# DW1000Breakout.net
KiCad netlist of a schematic drawn in Altium Designer
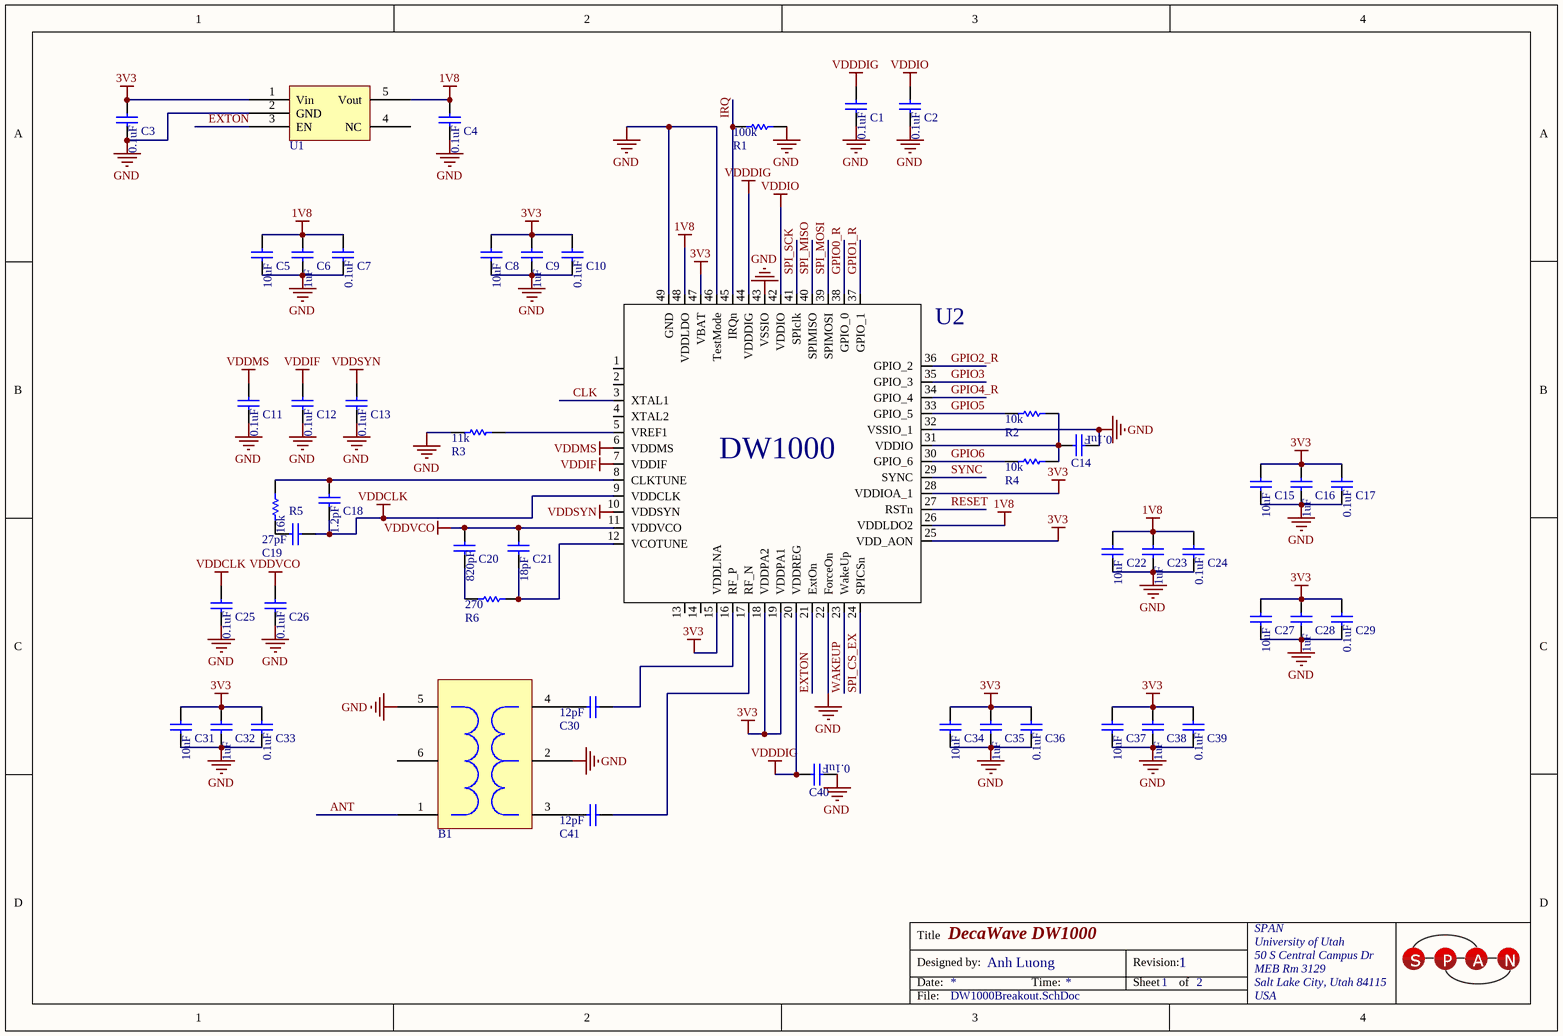
[diagram p0: DW1000Breakout.SchDoc]

(export (version "E")
  (design (tool "Eeschema 10.0.6"))
  (components
    (comp (ref "B1")
      (value "HHM1595A1")
      (footprint "BALUN")
      (description "XFMR BALUN RF 3.0-8.0GHZ UWB SMD")
      (fields (field (name "MANUFACTURER") "TDK Corporation"))
      (libsource (lib "DW1000Breakout") (part "HHM1595A1"))
    )
    (comp (ref "C1")
      (value "GRM188R71C104KA01D")
      (footprint "CAPC1608X08N (0603)")
      (description "CAP CER 0.1UF 16V 10% X7R 0603")
      (fields
        (field (name "MANUFACTURER") "Murata Electronics North America")
        (field (name "TOLERANCE") "±10%")
      )
      (libsource (lib "DW1000Breakout") (part "GRM188R71C104KA01D"))
    )
    (comp (ref "C2")
      (value "GRM188R71C104KA01D")
      (footprint "CAPC1608X08N (0603)")
      (description "CAP CER 0.1UF 16V 10% X7R 0603")
      (fields
        (field (name "MANUFACTURER") "Murata Electronics North America")
        (field (name "TOLERANCE") "±10%")
      )
      (libsource (lib "DW1000Breakout") (part "GRM188R71C104KA01D"))
    )
    (comp (ref "C3")
      (value "GRM188R71C104KA01D")
      (footprint "CAPC1608X08N (0603)")
      (description "CAP CER 0.1UF 16V 10% X7R 0603")
      (fields
        (field (name "MANUFACTURER") "Murata Electronics North America")
        (field (name "TOLERANCE") "±10%")
      )
      (libsource (lib "DW1000Breakout") (part "GRM188R71C104KA01D"))
    )
    (comp (ref "C4")
      (value "GRM188R71C104KA01D")
      (footprint "CAPC1608X08N (0603)")
      (description "CAP CER 0.1UF 16V 10% X7R 0603")
      (fields
        (field (name "MANUFACTURER") "Murata Electronics North America")
        (field (name "TOLERANCE") "±10%")
      )
      (libsource (lib "DW1000Breakout") (part "GRM188R71C104KA01D"))
    )
    (comp (ref "C5")
      (value "GRM188R60J106ME47D")
      (footprint "CAPC1608X08N (0603)")
      (description "CAP CER 10UF 6.3V 20% X5R 0603")
      (fields
        (field (name "MANUFACTURER") "Murata Electronics North America")
        (field (name "TOLERANCE") "±20%")
      )
      (libsource (lib "DWM1000Breakout") (part "GRM188R60J106ME47D"))
    )
    (comp (ref "C6")
      (value "GRM188R61A105KA61D")
      (footprint "CAPC1608X08N (0603)")
      (description "CAP CER 1UF 10V 10% X5R 0603")
      (fields
        (field (name "MANUFACTURER") "Murata Electronics North America")
        (field (name "TOLERANCE") "±10%")
      )
      (libsource (lib "DWM1000Breakout") (part "GRM188R61A105KA61D"))
    )
    (comp (ref "C7")
      (value "GRM188R71C104KA01D")
      (footprint "CAPC1608X08N (0603)")
      (description "CAP CER 0.1UF 16V 10% X7R 0603")
      (fields
        (field (name "MANUFACTURER") "Murata Electronics North America")
        (field (name "TOLERANCE") "±10%")
      )
      (libsource (lib "DWM1000Breakout") (part "GRM188R71C104KA01D"))
    )
    (comp (ref "C8")
      (value "GRM188R60J106ME47D")
      (footprint "CAPC1608X08N (0603)")
      (description "CAP CER 10UF 6.3V 20% X5R 0603")
      (fields
        (field (name "MANUFACTURER") "Murata Electronics North America")
        (field (name "TOLERANCE") "±20%")
      )
      (libsource (lib "DWM1000Breakout") (part "GRM188R60J106ME47D"))
    )
    (comp (ref "C9")
      (value "GRM188R61A105KA61D")
      (footprint "CAPC1608X08N (0603)")
      (description "CAP CER 1UF 10V 10% X5R 0603")
      (fields
        (field (name "MANUFACTURER") "Murata Electronics North America")
        (field (name "TOLERANCE") "±10%")
      )
      (libsource (lib "DWM1000Breakout") (part "GRM188R61A105KA61D"))
    )
    (comp (ref "C10")
      (value "GRM188R71C104KA01D")
      (footprint "CAPC1608X08N (0603)")
      (description "CAP CER 0.1UF 16V 10% X7R 0603")
      (fields
        (field (name "MANUFACTURER") "Murata Electronics North America")
        (field (name "TOLERANCE") "±10%")
      )
      (libsource (lib "DWM1000Breakout") (part "GRM188R71C104KA01D"))
    )
    (comp (ref "C11")
      (value "GRM188R71C104KA01D")
      (footprint "CAPC1608X08N (0603)")
      (description "CAP CER 0.1UF 16V 10% X7R 0603")
      (fields
        (field (name "MANUFACTURER") "Murata Electronics North America")
        (field (name "TOLERANCE") "±10%")
      )
      (libsource (lib "DW1000Breakout") (part "GRM188R71C104KA01D"))
    )
    (comp (ref "C12")
      (value "GRM188R71C104KA01D")
      (footprint "CAPC1608X08N (0603)")
      (description "CAP CER 0.1UF 16V 10% X7R 0603")
      (fields
        (field (name "MANUFACTURER") "Murata Electronics North America")
        (field (name "TOLERANCE") "±10%")
      )
      (libsource (lib "DW1000Breakout") (part "GRM188R71C104KA01D"))
    )
    (comp (ref "C13")
      (value "GRM188R71C104KA01D")
      (footprint "CAPC1608X08N (0603)")
      (description "CAP CER 0.1UF 16V 10% X7R 0603")
      (fields
        (field (name "MANUFACTURER") "Murata Electronics North America")
        (field (name "TOLERANCE") "±10%")
      )
      (libsource (lib "DW1000Breakout") (part "GRM188R71C104KA01D"))
    )
    (comp (ref "C14")
      (value "GRM188R71C104KA01D")
      (footprint "CAPC1608X08N (0603)")
      (description "CAP CER 0.1UF 16V 10% X7R 0603")
      (fields
        (field (name "MANUFACTURER") "Murata Electronics North America")
        (field (name "TOLERANCE") "±10%")
      )
      (libsource (lib "DW1000Breakout") (part "GRM188R71C104KA01D"))
    )
    (comp (ref "C15")
      (value "GRM188R60J106ME47D")
      (footprint "CAPC1608X08N (0603)")
      (description "CAP CER 10UF 6.3V 20% X5R 0603")
      (fields
        (field (name "MANUFACTURER") "Murata Electronics North America")
        (field (name "TOLERANCE") "±20%")
      )
      (libsource (lib "DWM1000Breakout") (part "GRM188R60J106ME47D"))
    )
    (comp (ref "C16")
      (value "GRM188R61A105KA61D")
      (footprint "CAPC1608X08N (0603)")
      (description "CAP CER 1UF 10V 10% X5R 0603")
      (fields
        (field (name "MANUFACTURER") "Murata Electronics North America")
        (field (name "TOLERANCE") "±10%")
      )
      (libsource (lib "DWM1000Breakout") (part "GRM188R61A105KA61D"))
    )
    (comp (ref "C17")
      (value "GRM188R71C104KA01D")
      (footprint "CAPC1608X08N (0603)")
      (description "CAP CER 0.1UF 16V 10% X7R 0603")
      (fields
        (field (name "MANUFACTURER") "Murata Electronics North America")
        (field (name "TOLERANCE") "±10%")
      )
      (libsource (lib "DWM1000Breakout") (part "GRM188R71C104KA01D"))
    )
    (comp (ref "C18")
      (value "GRM1885C1H1R2CA01D")
      (footprint "CAPC1608X08N (0603)")
      (description "CAP CER 1.2PF 50V NP0 0603")
      (fields
        (field (name "MANUFACTURER") "Murata Electronics North America")
        (field (name "TOLERANCE") "±0.25pF")
      )
      (libsource (lib "DW1000Breakout") (part "GRM1885C1H1R2CA01D"))
    )
    (comp (ref "C19")
      (value "GRM1885C1H270JA01D")
      (footprint "CAPC1608X08N (0603)")
      (description "CAP CER 27PF 50V NP0 0603")
      (fields
        (field (name "MANUFACTURER") "Murata Electronics North America")
        (field (name "TOLERANCE") "±5%")
      )
      (libsource (lib "DW1000Breakout") (part "GRM1885C1H270JA01D"))
    )
    (comp (ref "C20")
      (value "GRM188R71H821KA01D")
      (footprint "CAPC1608X08N (0603)")
      (description "CAP CER 820PF 50V X7R 0603")
      (fields
        (field (name "MANUFACTURER") "Murata Electronics North America")
        (field (name "TOLERANCE") "±10%")
      )
      (libsource (lib "DW1000Breakout") (part "GRM188R71H821KA01D"))
    )
    (comp (ref "C21")
      (value "GRM1885C1H180JA01D")
      (footprint "CAPC1608X08N (0603)")
      (description "CAP CER 18PF 50V NP0 0603")
      (fields
        (field (name "MANUFACTURER") "Murata Electronics North America")
        (field (name "TOLERANCE") "±5%")
      )
      (libsource (lib "DW1000Breakout") (part "GRM1885C1H180JA01D"))
    )
    (comp (ref "C22")
      (value "GRM188R60J106ME47D")
      (footprint "CAPC1608X08N (0603)")
      (description "CAP CER 10UF 6.3V 20% X5R 0603")
      (fields
        (field (name "MANUFACTURER") "Murata Electronics North America")
        (field (name "TOLERANCE") "±20%")
      )
      (libsource (lib "DWM1000Breakout") (part "GRM188R60J106ME47D"))
    )
    (comp (ref "C23")
      (value "GRM188R61A105KA61D")
      (footprint "CAPC1608X08N (0603)")
      (description "CAP CER 1UF 10V 10% X5R 0603")
      (fields
        (field (name "MANUFACTURER") "Murata Electronics North America")
        (field (name "TOLERANCE") "±10%")
      )
      (libsource (lib "DWM1000Breakout") (part "GRM188R61A105KA61D"))
    )
    (comp (ref "C24")
      (value "GRM188R71C104KA01D")
      (footprint "CAPC1608X08N (0603)")
      (description "CAP CER 0.1UF 16V 10% X7R 0603")
      (fields
        (field (name "MANUFACTURER") "Murata Electronics North America")
        (field (name "TOLERANCE") "±10%")
      )
      (libsource (lib "DWM1000Breakout") (part "GRM188R71C104KA01D"))
    )
    (comp (ref "C25")
      (value "GRM188R71C104KA01D")
      (footprint "CAPC1608X08N (0603)")
      (description "CAP CER 0.1UF 16V 10% X7R 0603")
      (fields
        (field (name "MANUFACTURER") "Murata Electronics North America")
        (field (name "TOLERANCE") "±10%")
      )
      (libsource (lib "DWM1000Breakout") (part "GRM188R71C104KA01D"))
    )
    (comp (ref "C26")
      (value "GRM188R71C104KA01D")
      (footprint "CAPC1608X08N (0603)")
      (description "CAP CER 0.1UF 16V 10% X7R 0603")
      (fields
        (field (name "MANUFACTURER") "Murata Electronics North America")
        (field (name "TOLERANCE") "±10%")
      )
      (libsource (lib "DWM1000Breakout") (part "GRM188R71C104KA01D"))
    )
    (comp (ref "C27")
      (value "GRM188R60J106ME47D")
      (footprint "CAPC1608X08N (0603)")
      (description "CAP CER 10UF 6.3V 20% X5R 0603")
      (fields
        (field (name "MANUFACTURER") "Murata Electronics North America")
        (field (name "TOLERANCE") "±20%")
      )
      (libsource (lib "DWM1000Breakout") (part "GRM188R60J106ME47D"))
    )
    (comp (ref "C28")
      (value "GRM188R61A105KA61D")
      (footprint "CAPC1608X08N (0603)")
      (description "CAP CER 1UF 10V 10% X5R 0603")
      (fields
        (field (name "MANUFACTURER") "Murata Electronics North America")
        (field (name "TOLERANCE") "±10%")
      )
      (libsource (lib "DWM1000Breakout") (part "GRM188R61A105KA61D"))
    )
    (comp (ref "C29")
      (value "GRM188R71C104KA01D")
      (footprint "CAPC1608X08N (0603)")
      (description "CAP CER 0.1UF 16V 10% X7R 0603")
      (fields
        (field (name "MANUFACTURER") "Murata Electronics North America")
        (field (name "TOLERANCE") "±10%")
      )
      (libsource (lib "DWM1000Breakout") (part "GRM188R71C104KA01D"))
    )
    (comp (ref "C30")
      (value "GRM1885C1H120JA01D")
      (footprint "CAPC1608X08N (0603)")
      (description "CAP CER 12PF 50V NP0 0603")
      (fields
        (field (name "MANUFACTURER") "Murata Electronics North America")
        (field (name "TOLERANCE") "±5%")
      )
      (libsource (lib "DW1000Breakout") (part "GRM1885C1H120JA01D"))
    )
    (comp (ref "C31")
      (value "GRM188R60J106ME47D")
      (footprint "CAPC1608X08N (0603)")
      (description "CAP CER 10UF 6.3V 20% X5R 0603")
      (fields
        (field (name "MANUFACTURER") "Murata Electronics North America")
        (field (name "TOLERANCE") "±20%")
      )
      (libsource (lib "DWM1000Breakout") (part "GRM188R60J106ME47D"))
    )
    (comp (ref "C32")
      (value "GRM188R61A105KA61D")
      (footprint "CAPC1608X08N (0603)")
      (description "CAP CER 1UF 10V 10% X5R 0603")
      (fields
        (field (name "MANUFACTURER") "Murata Electronics North America")
        (field (name "TOLERANCE") "±10%")
      )
      (libsource (lib "DWM1000Breakout") (part "GRM188R61A105KA61D"))
    )
    (comp (ref "C33")
      (value "GRM188R71C104KA01D")
      (footprint "CAPC1608X08N (0603)")
      (description "CAP CER 0.1UF 16V 10% X7R 0603")
      (fields
        (field (name "MANUFACTURER") "Murata Electronics North America")
        (field (name "TOLERANCE") "±10%")
      )
      (libsource (lib "DWM1000Breakout") (part "GRM188R71C104KA01D"))
    )
    (comp (ref "C34")
      (value "GRM188R60J106ME47D")
      (footprint "CAPC1608X08N (0603)")
      (description "CAP CER 10UF 6.3V 20% X5R 0603")
      (fields
        (field (name "MANUFACTURER") "Murata Electronics North America")
        (field (name "TOLERANCE") "±20%")
      )
      (libsource (lib "DWM1000Breakout") (part "GRM188R60J106ME47D"))
    )
    (comp (ref "C35")
      (value "GRM188R61A105KA61D")
      (footprint "CAPC1608X08N (0603)")
      (description "CAP CER 1UF 10V 10% X5R 0603")
      (fields
        (field (name "MANUFACTURER") "Murata Electronics North America")
        (field (name "TOLERANCE") "±10%")
      )
      (libsource (lib "DWM1000Breakout") (part "GRM188R61A105KA61D"))
    )
    (comp (ref "C36")
      (value "GRM188R71C104KA01D")
      (footprint "CAPC1608X08N (0603)")
      (description "CAP CER 0.1UF 16V 10% X7R 0603")
      (fields
        (field (name "MANUFACTURER") "Murata Electronics North America")
        (field (name "TOLERANCE") "±10%")
      )
      (libsource (lib "DWM1000Breakout") (part "GRM188R71C104KA01D"))
    )
    (comp (ref "C37")
      (value "GRM188R60J106ME47D")
      (footprint "CAPC1608X08N (0603)")
      (description "CAP CER 10UF 6.3V 20% X5R 0603")
      (fields
        (field (name "MANUFACTURER") "Murata Electronics North America")
        (field (name "TOLERANCE") "±20%")
      )
      (libsource (lib "DWM1000Breakout") (part "GRM188R60J106ME47D"))
    )
    (comp (ref "C38")
      (value "GRM188R61A105KA61D")
      (footprint "CAPC1608X08N (0603)")
      (description "CAP CER 1UF 10V 10% X5R 0603")
      (fields
        (field (name "MANUFACTURER") "Murata Electronics North America")
        (field (name "TOLERANCE") "±10%")
      )
      (libsource (lib "DWM1000Breakout") (part "GRM188R61A105KA61D"))
    )
    (comp (ref "C39")
      (value "GRM188R71C104KA01D")
      (footprint "CAPC1608X08N (0603)")
      (description "CAP CER 0.1UF 16V 10% X7R 0603")
      (fields
        (field (name "MANUFACTURER") "Murata Electronics North America")
        (field (name "TOLERANCE") "±10%")
      )
      (libsource (lib "DWM1000Breakout") (part "GRM188R71C104KA01D"))
    )
    (comp (ref "C40")
      (value "GRM188R71C104KA01D")
      (footprint "CAPC1608X08N (0603)")
      (description "CAP CER 0.1UF 16V 10% X7R 0603")
      (fields
        (field (name "MANUFACTURER") "Murata Electronics North America")
        (field (name "TOLERANCE") "±10%")
      )
      (libsource (lib "DW1000Breakout") (part "GRM188R71C104KA01D"))
    )
    (comp (ref "C41")
      (value "GRM1885C1H120JA01D")
      (footprint "CAPC1608X08N (0603)")
      (description "CAP CER 12PF 50V NP0 0603")
      (fields
        (field (name "MANUFACTURER") "Murata Electronics North America")
        (field (name "TOLERANCE") "±5%")
      )
      (libsource (lib "DW1000Breakout") (part "GRM1885C1H120JA01D"))
    )
    (comp (ref "R1")
      (value "MCR03ERTJ104")
      (footprint "RESC1608X06N (0603)")
      (description "RES SMD 100K OHM 5% 1/10W 0603")
      (fields (field (name "MANUFACTURER") "Rohm Semiconductor") (field (name "TOLERANCE") "±5%"))
      (libsource (lib "DW1000Breakout") (part "MCR03ERTJ104"))
    )
    (comp (ref "R2")
      (value "MCR03ERTJ103")
      (footprint "RESC1608X06N (0603)")
      (description "RES 10K OHM 1/10W 5% 0603 SMD")
      (fields (field (name "MANUFACTURER") "Rohm Semiconductor") (field (name "TOLERANCE") "±5%"))
      (libsource (lib "DW1000Breakout") (part "MCR03ERTJ103"))
    )
    (comp (ref "R3")
      (value "MCR03ERTJ113")
      (footprint "RESC1608X06N (0603)")
      (description "RES SMD 11K OHM 5% 1/10W 0603")
      (fields (field (name "MANUFACTURER") "Rohm Semiconductor") (field (name "TOLERANCE") "±5%"))
      (libsource (lib "DW1000Breakout") (part "MCR03ERTJ113"))
    )
    (comp (ref "R4")
      (value "MCR03ERTJ103")
      (footprint "RESC1608X06N (0603)")
      (description "RES 10K OHM 1/10W 5% 0603 SMD")
      (fields (field (name "MANUFACTURER") "Rohm Semiconductor") (field (name "TOLERANCE") "±5%"))
      (libsource (lib "DW1000Breakout") (part "MCR03ERTJ103"))
    )
    (comp (ref "R5")
      (value "MCR03ERTJ163")
      (footprint "RESC1608X06N (0603)")
      (description "RES SMD 16K OHM 5% 1/10W 0603")
      (fields (field (name "MANUFACTURER") "Rohm Semiconductor") (field (name "TOLERANCE") "±5%"))
      (libsource (lib "DW1000Breakout") (part "MCR03ERTJ163"))
    )
    (comp (ref "R6")
      (value "MCR03ERTJ271")
      (footprint "RESC1608X06N (0603)")
      (description "RES SMD 270 OHM 5% 1/10W 0603")
      (fields (field (name "MANUFACTURER") "Rohm Semiconductor") (field (name "TOLERANCE") "±5%"))
      (libsource (lib "DW1000Breakout") (part "MCR03ERTJ271"))
    )
    (comp (ref "U1")
      (value "LP5907MFX-1.8/NOPB")
      (footprint "SOT95P280X145-5N")
      (description "IC REG LDO 1.8V 0.25A SOT23-5")
      (fields (field (name "MANUFACTURER") "Texas Instruments"))
      (libsource (lib "DW1000Breakout") (part "LP5907MFX-1.8/NOPB"))
    )
    (comp (ref "U2")
      (value "DW1000 IC")
      (footprint "QFN-48")
      (description "UWB DW1000")
      (fields (field (name "PART NUMBER") "DW1000_QFN") (field (name "MANUFACTURER") "Decawave Ltd."))
      (libsource (lib "DW1000") (part "DW1000_QFN_48"))
    )
  )
  (nets
    (net (code "1") (name "/ANT") (class "Default")
      (node (ref "B1") (pin "1") (pinfunction "1_1") (pintype "passive"))
    )
    (net (code "2") (name "/CLK") (class "Default")
      (node (ref "U2") (pin "3") (pinfunction "XTAL1_3") (pintype "passive"))
    )
    (net (code "3") (name "/EXTON") (class "Default")
      (node (ref "U1") (pin "3") (pinfunction "EN_3") (pintype "passive"))
      (node (ref "U2") (pin "21") (pinfunction "ExtOn_21") (pintype "passive"))
    )
    (net (code "4") (name "/GPIO0_R") (class "Default")
      (node (ref "U2") (pin "38") (pinfunction "GPIO_0_38") (pintype "passive"))
    )
    (net (code "5") (name "/GPIO1_R") (class "Default")
      (node (ref "U2") (pin "37") (pinfunction "GPIO_1_37") (pintype "passive"))
    )
    (net (code "6") (name "/GPIO2_R") (class "Default")
      (node (ref "U2") (pin "36") (pinfunction "GPIO_2_36") (pintype "passive"))
    )
    (net (code "7") (name "/GPIO3") (class "Default")
      (node (ref "U2") (pin "35") (pinfunction "GPIO_3_35") (pintype "passive"))
    )
    (net (code "8") (name "/GPIO4_R") (class "Default")
      (node (ref "U2") (pin "34") (pinfunction "GPIO_4_34") (pintype "passive"))
    )
    (net (code "9") (name "/GPIO5") (class "Default")
      (node (ref "R2") (pin "1") (pinfunction "1_1") (pintype "passive"))
      (node (ref "U2") (pin "33") (pinfunction "GPIO_5_33") (pintype "passive"))
    )
    (net (code "10") (name "/GPIO6") (class "Default")
      (node (ref "R4") (pin "1") (pinfunction "1_1") (pintype "passive"))
      (node (ref "U2") (pin "30") (pinfunction "GPIO_6_30") (pintype "passive"))
    )
    (net (code "11") (name "/IRQ") (class "Default")
      (node (ref "R1") (pin "1") (pinfunction "1_1") (pintype "passive"))
      (node (ref "U2") (pin "45") (pinfunction "IRQn_45") (pintype "passive"))
    )
    (net (code "12") (name "/RESET") (class "Default")
      (node (ref "U2") (pin "27") (pinfunction "RSTn_27") (pintype "passive"))
    )
    (net (code "13") (name "/SPI_CS_EX") (class "Default")
      (node (ref "U2") (pin "24") (pinfunction "SPICSn_24") (pintype "passive"))
    )
    (net (code "14") (name "/SPI_MISO") (class "Default")
      (node (ref "U2") (pin "40") (pinfunction "SPIMISO_40") (pintype "passive"))
    )
    (net (code "15") (name "/SPI_MOSI") (class "Default")
      (node (ref "U2") (pin "39") (pinfunction "SPIMOSI_39") (pintype "passive"))
    )
    (net (code "16") (name "/SPI_SCK") (class "Default")
      (node (ref "U2") (pin "41") (pinfunction "SPIclk_41") (pintype "passive"))
    )
    (net (code "17") (name "/SYNC") (class "Default")
      (node (ref "U2") (pin "29") (pinfunction "SYNC_29") (pintype "passive"))
    )
    (net (code "18") (name "/WAKEUP") (class "Default")
      (node (ref "U2") (pin "23") (pinfunction "WakeUp_23") (pintype "passive"))
    )
    (net (code "19") (name "1V8") (class "Default")
      (node (ref "C22") (pin "2") (pinfunction "2_2") (pintype "passive"))
      (node (ref "C23") (pin "2") (pinfunction "2_2") (pintype "passive"))
      (node (ref "C24") (pin "2") (pinfunction "2_2") (pintype "passive"))
      (node (ref "C4") (pin "2") (pinfunction "2_2") (pintype "passive"))
      (node (ref "C5") (pin "2") (pinfunction "2_2") (pintype "passive"))
      (node (ref "C6") (pin "2") (pinfunction "2_2") (pintype "passive"))
      (node (ref "C7") (pin "2") (pinfunction "2_2") (pintype "passive"))
      (node (ref "U1") (pin "5") (pinfunction "Vout_5") (pintype "passive"))
      (node (ref "U2") (pin "26") (pinfunction "VDDLDO2_26") (pintype "passive"))
      (node (ref "U2") (pin "48") (pinfunction "VDDLDO_48") (pintype "passive"))
    )
    (net (code "20") (name "3V3") (class "Default")
      (node (ref "C10") (pin "2") (pinfunction "2_2") (pintype "passive"))
      (node (ref "C15") (pin "2") (pinfunction "2_2") (pintype "passive"))
      (node (ref "C16") (pin "2") (pinfunction "2_2") (pintype "passive"))
      (node (ref "C17") (pin "2") (pinfunction "2_2") (pintype "passive"))
      (node (ref "C27") (pin "2") (pinfunction "2_2") (pintype "passive"))
      (node (ref "C28") (pin "2") (pinfunction "2_2") (pintype "passive"))
      (node (ref "C29") (pin "2") (pinfunction "2_2") (pintype "passive"))
      (node (ref "C3") (pin "2") (pinfunction "2_2") (pintype "passive"))
      (node (ref "C31") (pin "2") (pinfunction "2_2") (pintype "passive"))
      (node (ref "C32") (pin "2") (pinfunction "2_2") (pintype "passive"))
      (node (ref "C33") (pin "2") (pinfunction "2_2") (pintype "passive"))
      (node (ref "C34") (pin "2") (pinfunction "2_2") (pintype "passive"))
      (node (ref "C35") (pin "2") (pinfunction "2_2") (pintype "passive"))
      (node (ref "C36") (pin "2") (pinfunction "2_2") (pintype "passive"))
      (node (ref "C37") (pin "2") (pinfunction "2_2") (pintype "passive"))
      (node (ref "C38") (pin "2") (pinfunction "2_2") (pintype "passive"))
      (node (ref "C39") (pin "2") (pinfunction "2_2") (pintype "passive"))
      (node (ref "C8") (pin "2") (pinfunction "2_2") (pintype "passive"))
      (node (ref "C9") (pin "2") (pinfunction "2_2") (pintype "passive"))
      (node (ref "U1") (pin "1") (pinfunction "Vin_1") (pintype "passive"))
      (node (ref "U2") (pin "15") (pinfunction "VDDLNA_15") (pintype "passive"))
      (node (ref "U2") (pin "18") (pinfunction "VDDPA2_18") (pintype "passive"))
      (node (ref "U2") (pin "19") (pinfunction "VDDPA1_19") (pintype "passive"))
      (node (ref "U2") (pin "25") (pinfunction "VDD_AON_25") (pintype "passive"))
      (node (ref "U2") (pin "28") (pinfunction "VDDIOA_1_28") (pintype "passive"))
      (node (ref "U2") (pin "47") (pinfunction "VBAT_47") (pintype "passive"))
    )
    (net (code "21") (name "GND") (class "Default")
      (node (ref "B1") (pin "2") (pinfunction "2_2") (pintype "passive"))
      (node (ref "B1") (pin "5") (pinfunction "5_5") (pintype "passive"))
      (node (ref "C1") (pin "1") (pinfunction "1_1") (pintype "passive"))
      (node (ref "C10") (pin "1") (pinfunction "1_1") (pintype "passive"))
      (node (ref "C11") (pin "1") (pinfunction "1_1") (pintype "passive"))
      (node (ref "C12") (pin "1") (pinfunction "1_1") (pintype "passive"))
      (node (ref "C13") (pin "1") (pinfunction "1_1") (pintype "passive"))
      (node (ref "C14") (pin "1") (pinfunction "1_1") (pintype "passive"))
      (node (ref "C15") (pin "1") (pinfunction "1_1") (pintype "passive"))
      (node (ref "C16") (pin "1") (pinfunction "1_1") (pintype "passive"))
      (node (ref "C17") (pin "1") (pinfunction "1_1") (pintype "passive"))
      (node (ref "C2") (pin "1") (pinfunction "1_1") (pintype "passive"))
      (node (ref "C22") (pin "1") (pinfunction "1_1") (pintype "passive"))
      (node (ref "C23") (pin "1") (pinfunction "1_1") (pintype "passive"))
      (node (ref "C24") (pin "1") (pinfunction "1_1") (pintype "passive"))
      (node (ref "C25") (pin "1") (pinfunction "1_1") (pintype "passive"))
      (node (ref "C26") (pin "1") (pinfunction "1_1") (pintype "passive"))
      (node (ref "C27") (pin "1") (pinfunction "1_1") (pintype "passive"))
      (node (ref "C28") (pin "1") (pinfunction "1_1") (pintype "passive"))
      (node (ref "C29") (pin "1") (pinfunction "1_1") (pintype "passive"))
      (node (ref "C3") (pin "1") (pinfunction "1_1") (pintype "passive"))
      (node (ref "C31") (pin "1") (pinfunction "1_1") (pintype "passive"))
      (node (ref "C32") (pin "1") (pinfunction "1_1") (pintype "passive"))
      (node (ref "C33") (pin "1") (pinfunction "1_1") (pintype "passive"))
      (node (ref "C34") (pin "1") (pinfunction "1_1") (pintype "passive"))
      (node (ref "C35") (pin "1") (pinfunction "1_1") (pintype "passive"))
      (node (ref "C36") (pin "1") (pinfunction "1_1") (pintype "passive"))
      (node (ref "C37") (pin "1") (pinfunction "1_1") (pintype "passive"))
      (node (ref "C38") (pin "1") (pinfunction "1_1") (pintype "passive"))
      (node (ref "C39") (pin "1") (pinfunction "1_1") (pintype "passive"))
      (node (ref "C4") (pin "1") (pinfunction "1_1") (pintype "passive"))
      (node (ref "C40") (pin "1") (pinfunction "1_1") (pintype "passive"))
      (node (ref "C5") (pin "1") (pinfunction "1_1") (pintype "passive"))
      (node (ref "C6") (pin "1") (pinfunction "1_1") (pintype "passive"))
      (node (ref "C7") (pin "1") (pinfunction "1_1") (pintype "passive"))
      (node (ref "C8") (pin "1") (pinfunction "1_1") (pintype "passive"))
      (node (ref "C9") (pin "1") (pinfunction "1_1") (pintype "passive"))
      (node (ref "R1") (pin "2") (pinfunction "2_2") (pintype "passive"))
      (node (ref "R3") (pin "1") (pinfunction "1_1") (pintype "passive"))
      (node (ref "U1") (pin "2") (pinfunction "GND_2") (pintype "passive"))
      (node (ref "U2") (pin "22") (pinfunction "ForceOn_22") (pintype "passive"))
      (node (ref "U2") (pin "32") (pinfunction "VSSIO_1_32") (pintype "passive"))
      (node (ref "U2") (pin "43") (pinfunction "VSSIO_43") (pintype "passive"))
      (node (ref "U2") (pin "46") (pinfunction "TestMode_46") (pintype "passive"))
      (node (ref "U2") (pin "49") (pinfunction "GND_49") (pintype "passive"))
    )
    (net (code "22") (name "Net-(B1-Pad3)") (class "Default")
      (node (ref "B1") (pin "3") (pinfunction "3_3") (pintype "passive"))
      (node (ref "C41") (pin "1") (pinfunction "1_1") (pintype "passive"))
    )
    (net (code "23") (name "Net-(B1-Pad4)") (class "Default")
      (node (ref "B1") (pin "4") (pinfunction "4_4") (pintype "passive"))
      (node (ref "C30") (pin "1") (pinfunction "1_1") (pintype "passive"))
    )
    (net (code "24") (name "Net-(C14-Pad2)") (class "Default")
      (node (ref "C14") (pin "2") (pinfunction "2_2") (pintype "passive"))
      (node (ref "R2") (pin "2") (pinfunction "2_2") (pintype "passive"))
      (node (ref "R4") (pin "2") (pinfunction "2_2") (pintype "passive"))
      (node (ref "U2") (pin "31") (pinfunction "VDDIO_31") (pintype "passive"))
    )
    (net (code "25") (name "Net-(C19-Pad1)") (class "Default")
      (node (ref "C19") (pin "1") (pinfunction "1_1") (pintype "passive"))
      (node (ref "R5") (pin "1") (pinfunction "1_1") (pintype "passive"))
    )
    (net (code "26") (name "Net-(C20-Pad1)") (class "Default")
      (node (ref "C20") (pin "1") (pinfunction "1_1") (pintype "passive"))
      (node (ref "R6") (pin "1") (pinfunction "1_1") (pintype "passive"))
    )
    (net (code "27") (name "Net-(U2-CLKTUNE)") (class "Default")
      (node (ref "C18") (pin "2") (pinfunction "2_2") (pintype "passive"))
      (node (ref "R5") (pin "2") (pinfunction "2_2") (pintype "passive"))
      (node (ref "U2") (pin "8") (pinfunction "CLKTUNE_8") (pintype "passive"))
    )
    (net (code "28") (name "Net-(U2-RF_N)") (class "Default")
      (node (ref "C41") (pin "2") (pinfunction "2_2") (pintype "passive"))
      (node (ref "U2") (pin "17") (pinfunction "RF_N_17") (pintype "passive"))
    )
    (net (code "29") (name "Net-(U2-RF_P)") (class "Default")
      (node (ref "C30") (pin "2") (pinfunction "2_2") (pintype "passive"))
      (node (ref "U2") (pin "16") (pinfunction "RF_P_16") (pintype "passive"))
    )
    (net (code "30") (name "Net-(U2-VCOTUNE)") (class "Default")
      (node (ref "C21") (pin "1") (pinfunction "1_1") (pintype "passive"))
      (node (ref "R6") (pin "2") (pinfunction "2_2") (pintype "passive"))
      (node (ref "U2") (pin "12") (pinfunction "VCOTUNE_12") (pintype "passive"))
    )
    (net (code "31") (name "Net-(U2-VREF1)") (class "Default")
      (node (ref "R3") (pin "2") (pinfunction "2_2") (pintype "passive"))
      (node (ref "U2") (pin "5") (pinfunction "VREF1_5") (pintype "passive"))
    )
    (net (code "32") (name "VDDCLK") (class "Default")
      (node (ref "C18") (pin "1") (pinfunction "1_1") (pintype "passive"))
      (node (ref "C19") (pin "2") (pinfunction "2_2") (pintype "passive"))
      (node (ref "C25") (pin "2") (pinfunction "2_2") (pintype "passive"))
      (node (ref "U2") (pin "9") (pinfunction "VDDCLK_9") (pintype "passive"))
    )
    (net (code "33") (name "VDDDIG") (class "Default")
      (node (ref "C1") (pin "2") (pinfunction "2_2") (pintype "passive"))
      (node (ref "C40") (pin "2") (pinfunction "2_2") (pintype "passive"))
      (node (ref "U2") (pin "20") (pinfunction "VDDREG_20") (pintype "passive"))
      (node (ref "U2") (pin "44") (pinfunction "VDDDIG_44") (pintype "passive"))
    )
    (net (code "34") (name "VDDIF") (class "Default")
      (node (ref "C12") (pin "2") (pinfunction "2_2") (pintype "passive"))
      (node (ref "U2") (pin "7") (pinfunction "VDDIF_7") (pintype "passive"))
    )
    (net (code "35") (name "VDDIO") (class "Default")
      (node (ref "C2") (pin "2") (pinfunction "2_2") (pintype "passive"))
      (node (ref "U2") (pin "42") (pinfunction "VDDIO_42") (pintype "passive"))
    )
    (net (code "36") (name "VDDMS") (class "Default")
      (node (ref "C11") (pin "2") (pinfunction "2_2") (pintype "passive"))
      (node (ref "U2") (pin "6") (pinfunction "VDDMS_6") (pintype "passive"))
    )
    (net (code "37") (name "VDDSYN") (class "Default")
      (node (ref "C13") (pin "2") (pinfunction "2_2") (pintype "passive"))
      (node (ref "U2") (pin "10") (pinfunction "VDDSYN_10") (pintype "passive"))
    )
    (net (code "38") (name "VDDVCO") (class "Default")
      (node (ref "C20") (pin "2") (pinfunction "2_2") (pintype "passive"))
      (node (ref "C21") (pin "2") (pinfunction "2_2") (pintype "passive"))
      (node (ref "C26") (pin "2") (pinfunction "2_2") (pintype "passive"))
      (node (ref "U2") (pin "11") (pinfunction "VDDVCO_11") (pintype "passive"))
    )
    (net (code "39") (name "unconnected-(B1-Pad6)") (class "Default")
      (node (ref "B1") (pin "6") (pinfunction "6_6") (pintype "passive"))
    )
    (net (code "40") (name "unconnected-(U1-NC-Pad4)") (class "Default")
      (node (ref "U1") (pin "4") (pinfunction "NC_4") (pintype "passive"))
    )
    (net (code "41") (name "unconnected-(U2-Pad1)") (class "Default")
      (node (ref "U2") (pin "1") (pintype "passive"))
    )
    (net (code "42") (name "unconnected-(U2-Pad2)") (class "Default")
      (node (ref "U2") (pin "2") (pintype "passive"))
    )
    (net (code "43") (name "unconnected-(U2-Pad13)") (class "Default")
      (node (ref "U2") (pin "13") (pintype "passive"))
    )
    (net (code "44") (name "unconnected-(U2-Pad14)") (class "Default")
      (node (ref "U2") (pin "14") (pintype "passive"))
    )
    (net (code "45") (name "unconnected-(U2-XTAL2-Pad4)") (class "Default")
      (node (ref "U2") (pin "4") (pinfunction "XTAL2_4") (pintype "passive"))
    )
  )
)
